# photoduino_solenoid_valve_interface_v_1_.net
KiCad netlist of a schematic drawn in EAGLE
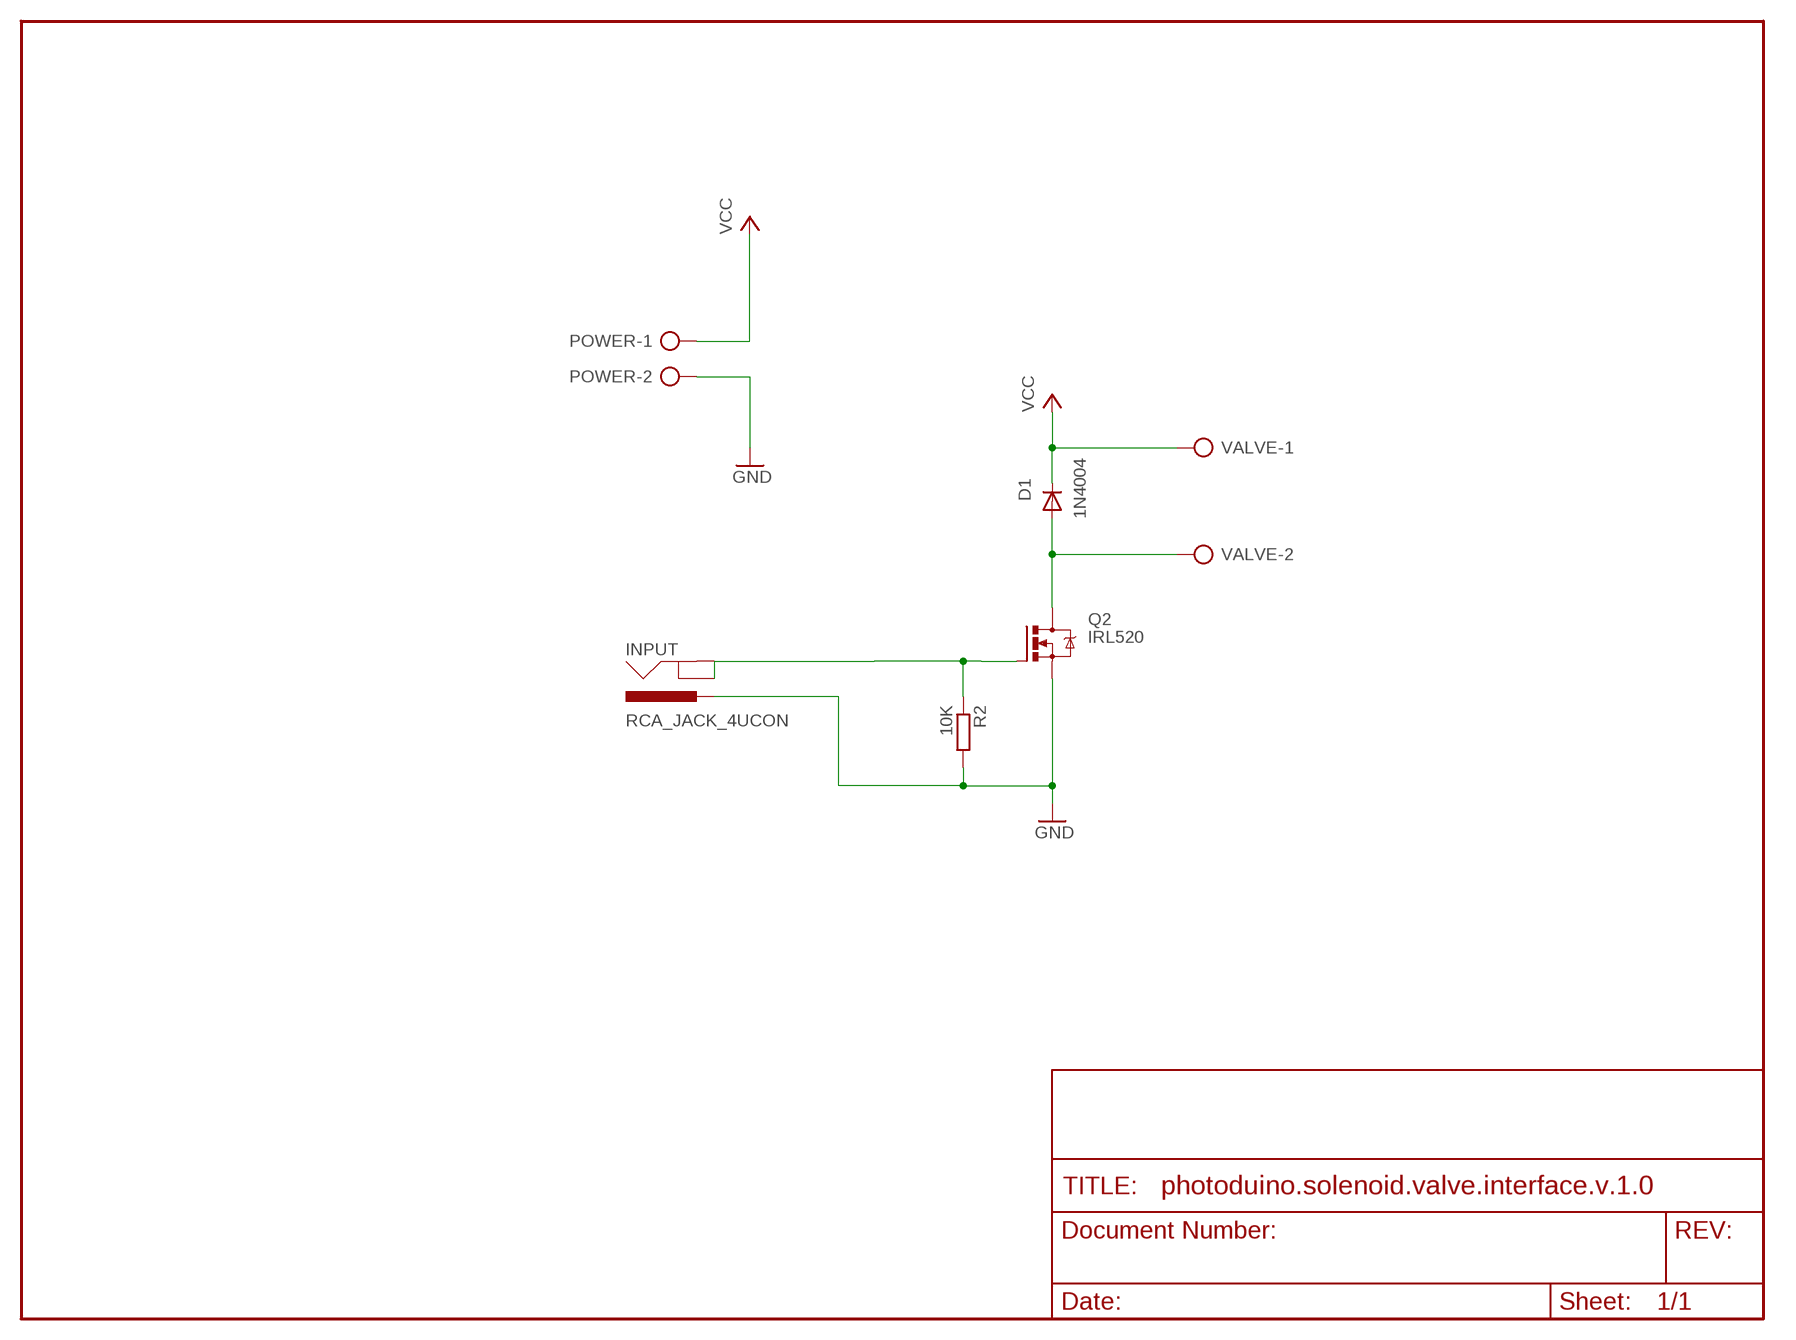
[diagram p0: schematic, sheet 1]

(export (version "E")
  (design (tool "Eeschema 10.0.6"))
  (components
    (comp (ref "D1")
      (value "1N4004")
      (footprint "eagle-import:DO41-10")
      (libsource (lib "eagle-import") (part "1N4004"))
    )
    (comp (ref "INPUT")
      (value "RCA_JACK_4UCON")
      (footprint "eagle-import:RCA_4UCON")
      (libsource (lib "eagle-import") (part "RCA_JACK_4UCON"))
    )
    (comp (ref "POWER")
      (value "AK500/2")
      (footprint "eagle-import:AK500_2")
      (libsource (lib "eagle-import") (part "AK500/2"))
    )
    (comp (ref "Q2")
      (value "IRL520")
      (footprint "eagle-import:TO220BH")
      (libsource (lib "eagle-import") (part "IRLZ44Z"))
    )
    (comp (ref "R2")
      (value "10K")
      (footprint "eagle-import:0207_7")
      (libsource (lib "eagle-import") (part "R-EU_0207/7"))
    )
    (comp (ref "VALVE")
      (value "AK500/2")
      (footprint "eagle-import:AK500_2")
      (libsource (lib "eagle-import") (part "AK500/2"))
    )
  )
  (nets
    (net (code "1") (name "GND") (class "Default")
      (node (ref "INPUT") (pin "BARREL") (pinfunction "BARREL_BARREL") (pintype "bidirectional"))
      (node (ref "POWER") (pin "2") (pinfunction "KL_2") (pintype "passive"))
      (node (ref "Q2") (pin "S") (pinfunction "S_S") (pintype "passive"))
      (node (ref "R2") (pin "2") (pinfunction "2_2") (pintype "passive"))
    )
    (net (code "2") (name "Net-(INPUT-PadBREAK)") (class "Default")
      (node (ref "INPUT") (pin "BREAK") (pinfunction "BREAK_BREAK") (pintype "bidirectional"))
      (node (ref "INPUT") (pin "SPRING") (pinfunction "SPRING_SPRING") (pintype "bidirectional"))
      (node (ref "Q2") (pin "G") (pinfunction "G_G") (pintype "passive"))
      (node (ref "R2") (pin "1") (pinfunction "1_1") (pintype "passive"))
    )
    (net (code "3") (name "Net-(VALVEB-KL)") (class "Default")
      (node (ref "D1") (pin "A") (pinfunction "A_A") (pintype "passive"))
      (node (ref "Q2") (pin "D") (pinfunction "D_D") (pintype "passive"))
      (node (ref "VALVE") (pin "2") (pinfunction "KL_2") (pintype "passive"))
    )
    (net (code "4") (name "VCC") (class "Default")
      (node (ref "D1") (pin "C") (pinfunction "C_C") (pintype "passive"))
      (node (ref "POWER") (pin "1") (pinfunction "KL_1") (pintype "passive"))
      (node (ref "VALVE") (pin "1") (pinfunction "KL_1") (pintype "passive"))
    )
  )
)
